# windowSensor.net
KiCad netlist of a schematic drawn in EAGLE
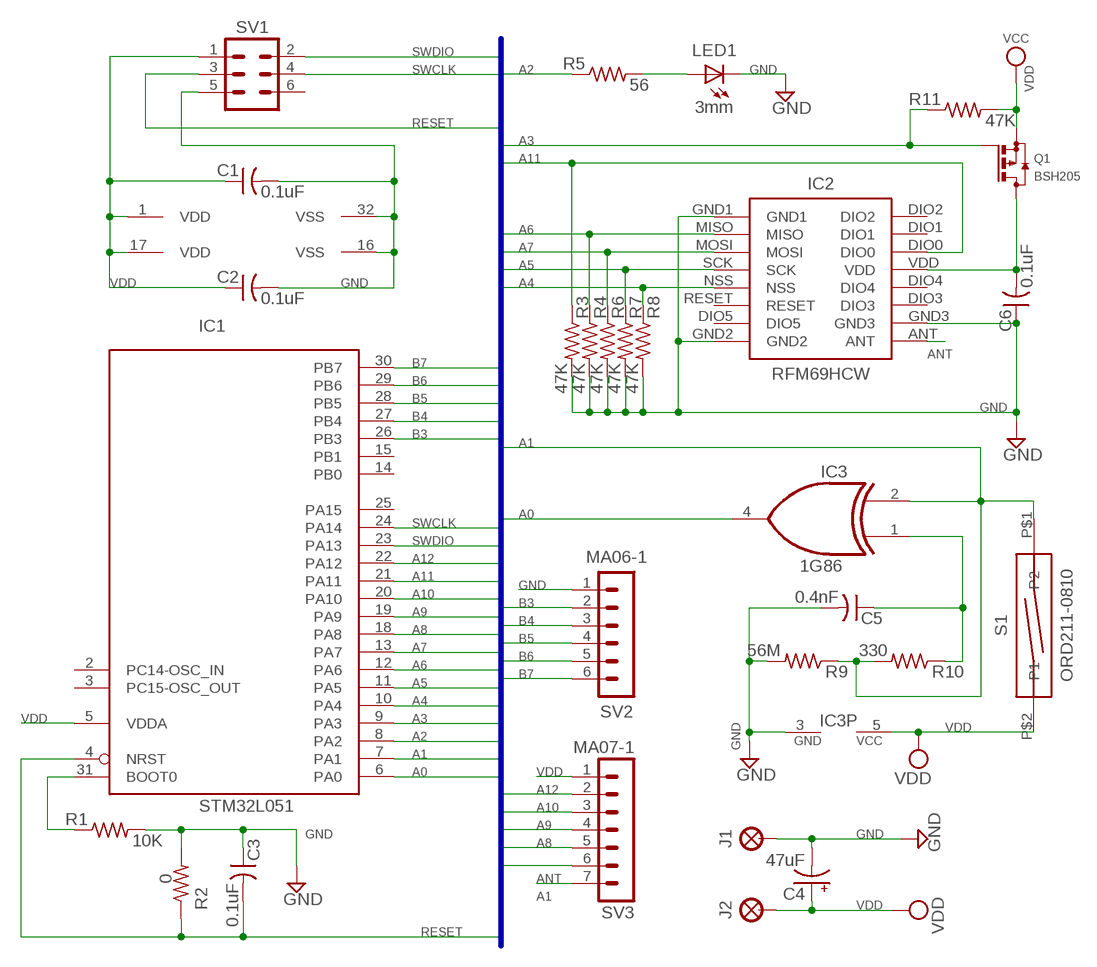
[diagram p0: schematic, sheet 1]

(export (version "E")
  (design (tool "Eeschema 10.0.6"))
  (components
    (comp (ref "C1")
      (value "0.1uF")
      (footprint "eagle-import:C0805")
      (libsource (lib "eagle-import") (part "C-US0805"))
    )
    (comp (ref "C2")
      (value "0.1uF")
      (footprint "eagle-import:C0805")
      (libsource (lib "eagle-import") (part "C-US0805"))
    )
    (comp (ref "C3")
      (value "0.1uF")
      (footprint "eagle-import:C0805")
      (libsource (lib "eagle-import") (part "C-US0805"))
    )
    (comp (ref "C4")
      (value "47uF")
      (footprint "eagle-import:CPOL0805")
      (libsource (lib "eagle-import") (part "CPOL-US0805"))
    )
    (comp (ref "C5")
      (value "0.4nF")
      (footprint "eagle-import:C0805")
      (libsource (lib "eagle-import") (part "C-US0805"))
    )
    (comp (ref "C6")
      (value "0.1uF")
      (footprint "eagle-import:C0805")
      (libsource (lib "eagle-import") (part "C-US0805"))
    )
    (comp (ref "IC1")
      (value "STM32L051")
      (footprint "eagle-import:LQFP32")
      (libsource (lib "eagle-import") (part "STM32L051KT6"))
    )
    (comp (ref "IC2")
      (value "RFM69HCW")
      (footprint "eagle-import:RFM69HCW")
      (libsource (lib "eagle-import") (part "RFM69HCW"))
    )
    (comp (ref "IC3")
      (value "1G86")
      (footprint "eagle-import:SC70-5")
      (libsource (lib "eagle-import") (part "741G86DCKAHC"))
    )
    (comp (ref "J1")
      (value "LSP30-LONG")
      (footprint "eagle-import:LSP30-LONG")
      (libsource (lib "eagle-import") (part "LSP30-LONG"))
    )
    (comp (ref "J2")
      (value "LSP30-LONG")
      (footprint "eagle-import:LSP30-LONG")
      (libsource (lib "eagle-import") (part "LSP30-LONG"))
    )
    (comp (ref "LED1")
      (value "3mm")
      (footprint "eagle-import:LED3MM")
      (libsource (lib "eagle-import") (part "LED3MM"))
    )
    (comp (ref "Q1")
      (value "BSH205")
      (footprint "eagle-import:SOT23")
      (libsource (lib "eagle-import") (part "BSH205G2R"))
    )
    (comp (ref "R1")
      (value "10K")
      (footprint "eagle-import:R0805")
      (libsource (lib "eagle-import") (part "R-US0805"))
    )
    (comp (ref "R2")
      (value "0")
      (footprint "eagle-import:R0805")
      (libsource (lib "eagle-import") (part "R-US0805"))
    )
    (comp (ref "R3")
      (value "47K")
      (footprint "eagle-import:R0805")
      (libsource (lib "eagle-import") (part "R-US0805"))
    )
    (comp (ref "R4")
      (value "47K")
      (footprint "eagle-import:R0805")
      (libsource (lib "eagle-import") (part "R-US0805"))
    )
    (comp (ref "R5")
      (value "56")
      (footprint "eagle-import:R0805")
      (libsource (lib "eagle-import") (part "R-US0805"))
    )
    (comp (ref "R6")
      (value "47K")
      (footprint "eagle-import:R0805")
      (libsource (lib "eagle-import") (part "R-US0805"))
    )
    (comp (ref "R7")
      (value "47K")
      (footprint "eagle-import:R0805")
      (libsource (lib "eagle-import") (part "R-US0805"))
    )
    (comp (ref "R8")
      (value "47K")
      (footprint "eagle-import:R0805")
      (libsource (lib "eagle-import") (part "R-US0805"))
    )
    (comp (ref "R9")
      (value "56M")
      (footprint "eagle-import:R0805")
      (libsource (lib "eagle-import") (part "R-US0805"))
    )
    (comp (ref "R10")
      (value "330")
      (footprint "eagle-import:R0805")
      (libsource (lib "eagle-import") (part "R-US0805"))
    )
    (comp (ref "R11")
      (value "47K")
      (footprint "eagle-import:R0805")
      (libsource (lib "eagle-import") (part "R-US0805"))
    )
    (comp (ref "S1")
      (value "ORD211-0810")
      (footprint "eagle-import:ORD211-0810")
      (libsource (lib "eagle-import") (part "ORD211-0810"))
    )
    (comp (ref "SV1")
      (value "SWD")
      (footprint "eagle-import:MA03-2")
      (libsource (lib "eagle-import") (part "MA03-2"))
    )
    (comp (ref "SV2")
      (value "MA06-1")
      (footprint "eagle-import:MA06-1-NO-PL")
      (libsource (lib "eagle-import") (part "MA06-1"))
    )
    (comp (ref "SV3")
      (value "MA07-1")
      (footprint "eagle-import:MA07-1-NO-PL")
      (libsource (lib "eagle-import") (part "MA07-1NO-PL"))
    )
  )
  (nets
    (net (code "1") (name "/A0") (class "Default")
      (node (ref "IC1") (pin "6") (pinfunction "PA0_6") (pintype "bidirectional"))
      (node (ref "IC3") (pin "4") (pinfunction "O_4") (pintype "output"))
    )
    (net (code "2") (name "/A1") (class "Default")
      (node (ref "IC1") (pin "7") (pinfunction "PA1_7") (pintype "bidirectional"))
      (node (ref "IC3") (pin "2") (pinfunction "I1_2") (pintype "input"))
      (node (ref "R10") (pin "2") (pinfunction "2_2") (pintype "passive"))
      (node (ref "R9") (pin "1") (pinfunction "1_1") (pintype "passive"))
      (node (ref "S1") (pin "P$1") (pinfunction "P2_P$1") (pintype "bidirectional"))
      (node (ref "SV3") (pin "6") (pinfunction "6_6") (pintype "passive"))
    )
    (net (code "3") (name "/A2") (class "Default")
      (node (ref "IC1") (pin "8") (pinfunction "PA2_8") (pintype "bidirectional"))
      (node (ref "R5") (pin "1") (pinfunction "1_1") (pintype "passive"))
    )
    (net (code "4") (name "/A3") (class "Default")
      (node (ref "IC1") (pin "9") (pinfunction "PA3_9") (pintype "bidirectional"))
      (node (ref "Q1") (pin "1") (pinfunction "G_1") (pintype "passive"))
      (node (ref "R11") (pin "1") (pinfunction "1_1") (pintype "passive"))
    )
    (net (code "5") (name "/A4") (class "Default")
      (node (ref "IC1") (pin "10") (pinfunction "PA4_10") (pintype "bidirectional"))
      (node (ref "IC2") (pin "NSS") (pinfunction "NSS_NSS") (pintype "bidirectional"))
      (node (ref "R8") (pin "1") (pinfunction "1_1") (pintype "passive"))
    )
    (net (code "6") (name "/A5") (class "Default")
      (node (ref "IC1") (pin "11") (pinfunction "PA5_11") (pintype "bidirectional"))
      (node (ref "IC2") (pin "SCK") (pinfunction "SCK_SCK") (pintype "bidirectional"))
      (node (ref "R7") (pin "1") (pinfunction "1_1") (pintype "passive"))
    )
    (net (code "7") (name "/A6") (class "Default")
      (node (ref "IC1") (pin "12") (pinfunction "PA6_12") (pintype "bidirectional"))
      (node (ref "IC2") (pin "MISO") (pinfunction "MISO_MISO") (pintype "bidirectional"))
      (node (ref "R4") (pin "1") (pinfunction "1_1") (pintype "passive"))
    )
    (net (code "8") (name "/A7") (class "Default")
      (node (ref "IC1") (pin "13") (pinfunction "PA7_13") (pintype "bidirectional"))
      (node (ref "IC2") (pin "MOSI") (pinfunction "MOSI_MOSI") (pintype "bidirectional"))
      (node (ref "R6") (pin "1") (pinfunction "1_1") (pintype "passive"))
    )
    (net (code "9") (name "/A8") (class "Default")
      (node (ref "IC1") (pin "18") (pinfunction "PA8_18") (pintype "bidirectional"))
      (node (ref "SV3") (pin "5") (pinfunction "5_5") (pintype "passive"))
    )
    (net (code "10") (name "/A9") (class "Default")
      (node (ref "IC1") (pin "19") (pinfunction "PA9_19") (pintype "bidirectional"))
      (node (ref "SV3") (pin "4") (pinfunction "4_4") (pintype "passive"))
    )
    (net (code "11") (name "/A10") (class "Default")
      (node (ref "IC1") (pin "20") (pinfunction "PA10_20") (pintype "bidirectional"))
      (node (ref "SV3") (pin "3") (pinfunction "3_3") (pintype "passive"))
    )
    (net (code "12") (name "/A11") (class "Default")
      (node (ref "IC1") (pin "21") (pinfunction "PA11_21") (pintype "bidirectional"))
      (node (ref "IC2") (pin "DIO0") (pinfunction "DIO0_DIO0") (pintype "bidirectional"))
      (node (ref "R3") (pin "1") (pinfunction "1_1") (pintype "passive"))
    )
    (net (code "13") (name "/A12") (class "Default")
      (node (ref "IC1") (pin "22") (pinfunction "PA12_22") (pintype "bidirectional"))
      (node (ref "SV3") (pin "2") (pinfunction "2_2") (pintype "passive"))
    )
    (net (code "14") (name "/ANT") (class "Default")
      (node (ref "IC2") (pin "ANT") (pinfunction "ANT_ANT") (pintype "bidirectional"))
      (node (ref "SV3") (pin "7") (pinfunction "7_7") (pintype "passive"))
    )
    (net (code "15") (name "/B3") (class "Default")
      (node (ref "IC1") (pin "26") (pinfunction "PB3_26") (pintype "bidirectional"))
      (node (ref "SV2") (pin "2") (pinfunction "2_2") (pintype "passive"))
    )
    (net (code "16") (name "/B4") (class "Default")
      (node (ref "IC1") (pin "27") (pinfunction "PB4_27") (pintype "bidirectional"))
      (node (ref "SV2") (pin "3") (pinfunction "3_3") (pintype "passive"))
    )
    (net (code "17") (name "/B5") (class "Default")
      (node (ref "IC1") (pin "28") (pinfunction "PB5_28") (pintype "bidirectional"))
      (node (ref "SV2") (pin "4") (pinfunction "4_4") (pintype "passive"))
    )
    (net (code "18") (name "/B6") (class "Default")
      (node (ref "IC1") (pin "29") (pinfunction "PB6_29") (pintype "bidirectional"))
      (node (ref "SV2") (pin "5") (pinfunction "5_5") (pintype "passive"))
    )
    (net (code "19") (name "/B7") (class "Default")
      (node (ref "IC1") (pin "30") (pinfunction "PB7_30") (pintype "bidirectional"))
      (node (ref "SV2") (pin "6") (pinfunction "6_6") (pintype "passive"))
    )
    (net (code "20") (name "/RESET") (class "Default")
      (node (ref "C3") (pin "2") (pinfunction "2_2") (pintype "passive"))
      (node (ref "IC1") (pin "4") (pinfunction "NRST_4") (pintype "bidirectional"))
      (node (ref "R2") (pin "1") (pinfunction "1_1") (pintype "passive"))
      (node (ref "SV1") (pin "3") (pinfunction "3_3") (pintype "passive"))
    )
    (net (code "21") (name "/SWCLK") (class "Default")
      (node (ref "IC1") (pin "24") (pinfunction "PA14_24") (pintype "bidirectional"))
      (node (ref "SV1") (pin "4") (pinfunction "4_4") (pintype "passive"))
    )
    (net (code "22") (name "/SWDIO") (class "Default")
      (node (ref "IC1") (pin "23") (pinfunction "PA13_23") (pintype "bidirectional"))
      (node (ref "SV1") (pin "2") (pinfunction "2_2") (pintype "passive"))
    )
    (net (code "23") (name "GND") (class "Default")
      (node (ref "C1") (pin "2") (pinfunction "2_2") (pintype "passive"))
      (node (ref "C2") (pin "2") (pinfunction "2_2") (pintype "passive"))
      (node (ref "C3") (pin "1") (pinfunction "1_1") (pintype "passive"))
      (node (ref "C4") (pin "2-") (pinfunction "-_2-") (pintype "passive"))
      (node (ref "C5") (pin "2") (pinfunction "2_2") (pintype "passive"))
      (node (ref "C6") (pin "1") (pinfunction "1_1") (pintype "passive"))
      (node (ref "IC1") (pin "16") (pinfunction "VSS_16") (pintype "power_in"))
      (node (ref "IC1") (pin "32") (pinfunction "VSS_32") (pintype "power_in"))
      (node (ref "IC2") (pin "GND1") (pinfunction "GND1_GND1") (pintype "bidirectional"))
      (node (ref "IC2") (pin "GND2") (pinfunction "GND2_GND2") (pintype "bidirectional"))
      (node (ref "IC2") (pin "GND3") (pinfunction "GND3_GND3") (pintype "bidirectional"))
      (node (ref "IC3") (pin "3") (pinfunction "GND_3") (pintype "power_in"))
      (node (ref "J1") (pin "MP") (pinfunction "MP_MP") (pintype "passive"))
      (node (ref "LED1") (pin "K") (pinfunction "C_K") (pintype "passive"))
      (node (ref "R1") (pin "2") (pinfunction "2_2") (pintype "passive"))
      (node (ref "R2") (pin "2") (pinfunction "2_2") (pintype "passive"))
      (node (ref "R3") (pin "2") (pinfunction "2_2") (pintype "passive"))
      (node (ref "R4") (pin "2") (pinfunction "2_2") (pintype "passive"))
      (node (ref "R6") (pin "2") (pinfunction "2_2") (pintype "passive"))
      (node (ref "R7") (pin "2") (pinfunction "2_2") (pintype "passive"))
      (node (ref "R8") (pin "2") (pinfunction "2_2") (pintype "passive"))
      (node (ref "R9") (pin "2") (pinfunction "2_2") (pintype "passive"))
      (node (ref "SV1") (pin "5") (pinfunction "5_5") (pintype "passive"))
      (node (ref "SV2") (pin "1") (pinfunction "1_1") (pintype "passive"))
    )
    (net (code "24") (name "Net-(IC1A-BOOT0)") (class "Default")
      (node (ref "IC1") (pin "31") (pinfunction "BOOT0_31") (pintype "input"))
      (node (ref "R1") (pin "1") (pinfunction "1_1") (pintype "passive"))
    )
    (net (code "25") (name "Net-(IC3A-I0)") (class "Default")
      (node (ref "C5") (pin "1") (pinfunction "1_1") (pintype "passive"))
      (node (ref "IC3") (pin "1") (pinfunction "I0_1") (pintype "input"))
      (node (ref "R10") (pin "1") (pinfunction "1_1") (pintype "passive"))
    )
    (net (code "26") (name "Net-(LED1-PadA)") (class "Default")
      (node (ref "LED1") (pin "A") (pinfunction "A_A") (pintype "passive"))
      (node (ref "R5") (pin "2") (pinfunction "2_2") (pintype "passive"))
    )
    (net (code "27") (name "Net-(Q1-D)") (class "Default")
      (node (ref "C6") (pin "2") (pinfunction "2_2") (pintype "passive"))
      (node (ref "IC2") (pin "VDD") (pinfunction "VDD_VDD") (pintype "bidirectional"))
      (node (ref "Q1") (pin "3") (pinfunction "D_3") (pintype "passive"))
    )
    (net (code "28") (name "VCC") (class "Default")
      (node (ref "C1") (pin "1") (pinfunction "1_1") (pintype "passive"))
      (node (ref "C2") (pin "1") (pinfunction "1_1") (pintype "passive"))
      (node (ref "C4") (pin "1+") (pinfunction "+_1+") (pintype "passive"))
      (node (ref "IC1") (pin "1") (pinfunction "VDD_1") (pintype "power_in"))
      (node (ref "IC1") (pin "17") (pinfunction "VDD_17") (pintype "power_in"))
      (node (ref "IC1") (pin "5") (pinfunction "VDDA_5") (pintype "power_in"))
      (node (ref "IC3") (pin "5") (pinfunction "VCC_5") (pintype "power_in"))
      (node (ref "J2") (pin "MP") (pinfunction "MP_MP") (pintype "passive"))
      (node (ref "Q1") (pin "2") (pinfunction "S_2") (pintype "passive"))
      (node (ref "R11") (pin "2") (pinfunction "2_2") (pintype "passive"))
      (node (ref "S1") (pin "P$2") (pinfunction "P1_P$2") (pintype "bidirectional"))
      (node (ref "SV1") (pin "1") (pinfunction "1_1") (pintype "passive"))
      (node (ref "SV3") (pin "1") (pinfunction "1_1") (pintype "passive"))
    )
    (net (code "29") (name "unconnected-(IC1A-PA15-Pad25)") (class "Default")
      (node (ref "IC1") (pin "25") (pinfunction "PA15_25") (pintype "bidirectional"))
    )
    (net (code "30") (name "unconnected-(IC1A-PB0-Pad14)") (class "Default")
      (node (ref "IC1") (pin "14") (pinfunction "PB0_14") (pintype "bidirectional"))
    )
    (net (code "31") (name "unconnected-(IC1A-PB1-Pad15)") (class "Default")
      (node (ref "IC1") (pin "15") (pinfunction "PB1_15") (pintype "bidirectional"))
    )
    (net (code "32") (name "unconnected-(IC1A-PC14-OSC_IN-Pad2)") (class "Default")
      (node (ref "IC1") (pin "2") (pinfunction "PC14-OSC_IN_2") (pintype "bidirectional"))
    )
    (net (code "33") (name "unconnected-(IC1A-PC15-OSC_OUT-Pad3)") (class "Default")
      (node (ref "IC1") (pin "3") (pinfunction "PC15-OSC_OUT_3") (pintype "bidirectional"))
    )
    (net (code "34") (name "unconnected-(IC2-PadDIO1)") (class "Default")
      (node (ref "IC2") (pin "DIO1") (pinfunction "DIO1_DIO1") (pintype "bidirectional"))
    )
    (net (code "35") (name "unconnected-(IC2-PadDIO2)") (class "Default")
      (node (ref "IC2") (pin "DIO2") (pinfunction "DIO2_DIO2") (pintype "bidirectional"))
    )
    (net (code "36") (name "unconnected-(IC2-PadDIO3)") (class "Default")
      (node (ref "IC2") (pin "DIO3") (pinfunction "DIO3_DIO3") (pintype "bidirectional"))
    )
    (net (code "37") (name "unconnected-(IC2-PadDIO4)") (class "Default")
      (node (ref "IC2") (pin "DIO4") (pinfunction "DIO4_DIO4") (pintype "bidirectional"))
    )
    (net (code "38") (name "unconnected-(IC2-PadDIO5)") (class "Default")
      (node (ref "IC2") (pin "DIO5") (pinfunction "DIO5_DIO5") (pintype "bidirectional"))
    )
    (net (code "39") (name "unconnected-(IC2-PadRESET)") (class "Default")
      (node (ref "IC2") (pin "RESET") (pinfunction "RESET_RESET") (pintype "bidirectional"))
    )
    (net (code "40") (name "unconnected-(SV1-Pad6)") (class "Default")
      (node (ref "SV1") (pin "6") (pinfunction "6_6") (pintype "passive"))
    )
  )
)
